# NG2094_Connector_A.net
KiCad netlist of a schematic drawn in Altium Designer
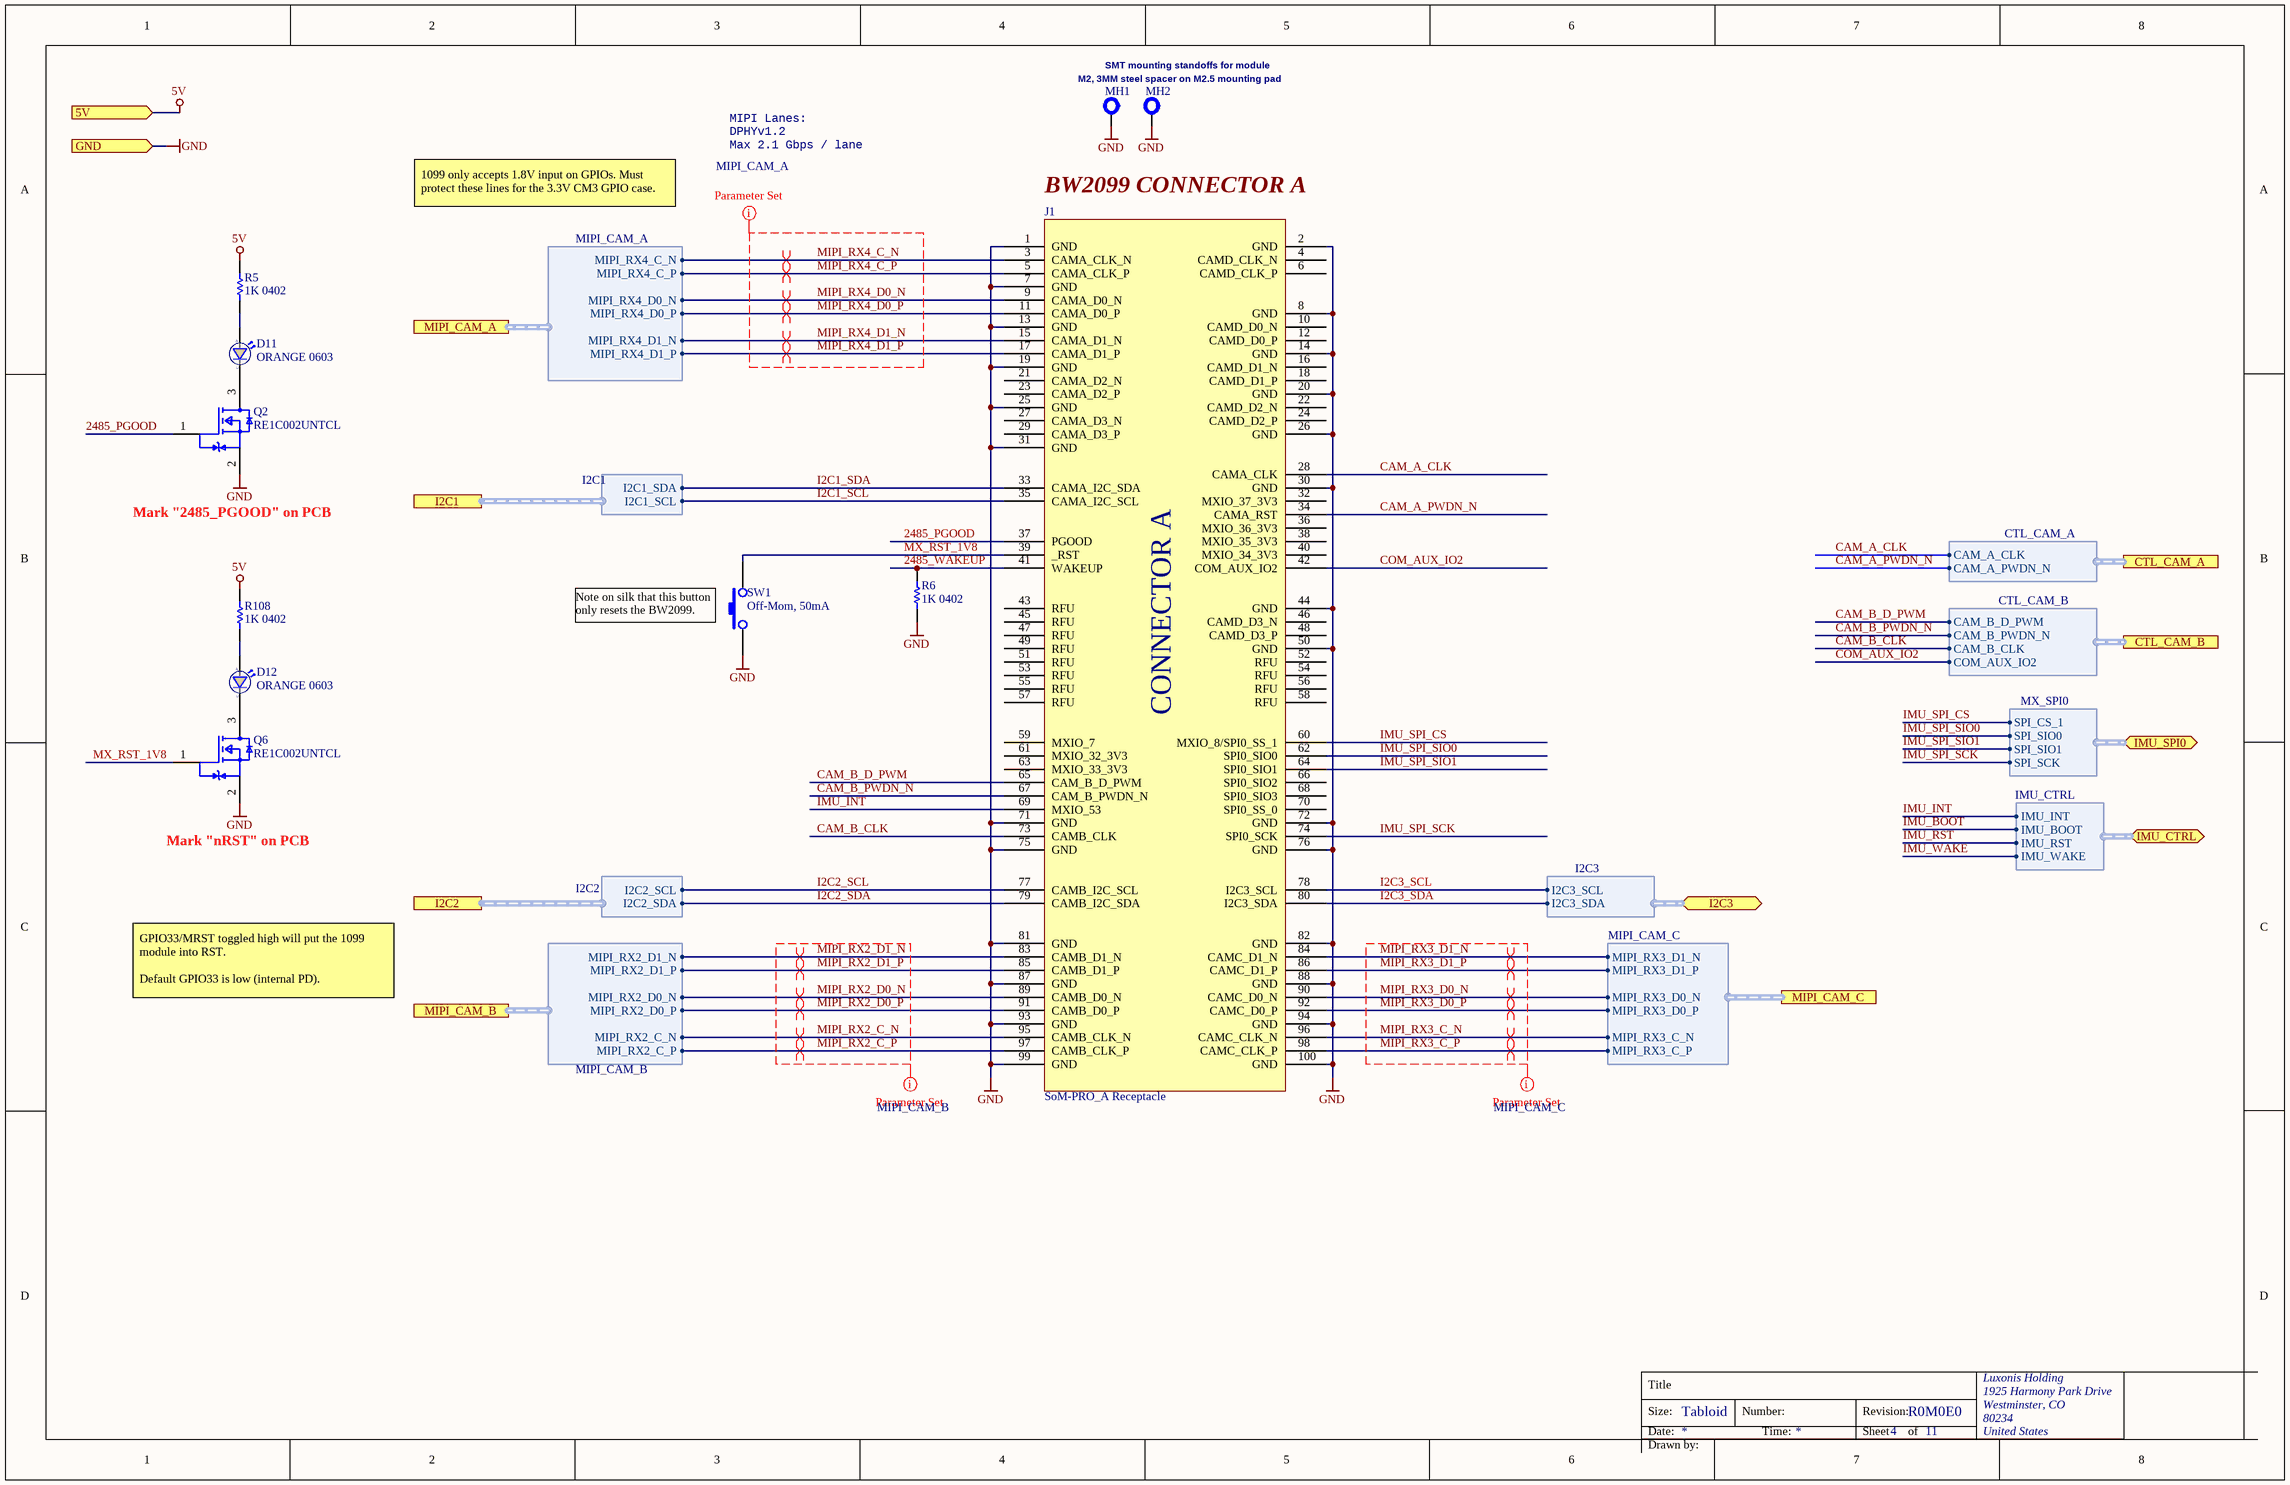
[diagram p0: NG2094_Connector_A.SchDoc]

(export (version "E")
  (design (tool "Eeschema 10.0.6"))
  (components
    (comp (ref "D11")
      (value "ORANGE 0603")
      (footprint "LuxonisMaster:SML_D1xx8W")
      (description "LED ORANGE DIFFUSED 0603 SMD Orange 605nm LED Indication - Discrete 2.2V 0603 (1608 Metric)")
      (libsource (lib "LuxonisMaster") (part "SML-D12D8WT86"))
    )
    (comp (ref "D12")
      (value "ORANGE 0603")
      (footprint "LuxonisMaster:SML_D1xx8W")
      (description "LED ORANGE DIFFUSED 0603 SMD Orange 605nm LED Indication - Discrete 2.2V 0603 (1608 Metric)")
      (libsource (lib "LuxonisMaster") (part "SML-D12D8WT86"))
    )
    (comp (ref "J1")
      (value "SoM-PRO_A Receptacle")
      (footprint "CON_A_BW2099_SoM_DF40HC-3.0-100DS-0.4V_minpad")
      (description "CONN RCPT 100POS 0.4MM SMD GOLD")
      (libsource (lib "BW2099_SoM") (part "DF40HC(3.0)-100DS-0.4V_SoM-PRO_A"))
    )
    (comp (ref "MH1")
      (value "M2, 3MM steel spacer on M2.5 mounting pad")
      (footprint "LuxonisMaster:9774030243R")
      (description "MP ROUND STANDOFF M2X0.4 STEEL 3MM")
      (libsource (lib "LuxonisMaster") (part "9774030243R"))
    )
    (comp (ref "MH2")
      (value "M2, 3MM steel spacer on M2.5 mounting pad")
      (footprint "LuxonisMaster:9774030243R")
      (description "MP ROUND STANDOFF M2X0.4 STEEL 3MM")
      (libsource (lib "LuxonisMaster") (part "9774030243R"))
    )
    (comp (ref "Q2")
      (value "RE1C002UNTCL")
      (footprint "LuxonisMaster:RE1C002UNTCL")
      (description "VISHAY - SI1062X-T1-GE3 - MOSFET Transistor, N Channel, 530 mA, 20 V, 0.35 ohm, 4.5 V, 1 V")
      (libsource (lib "LuxonisMaster") (part "RE1C002UNTCL"))
    )
    (comp (ref "Q6")
      (value "RE1C002UNTCL")
      (footprint "LuxonisMaster:RE1C002UNTCL")
      (description "VISHAY - SI1062X-T1-GE3 - MOSFET Transistor, N Channel, 530 mA, 20 V, 0.35 ohm, 4.5 V, 1 V")
      (libsource (lib "LuxonisMaster") (part "RE1C002UNTCL"))
    )
    (comp (ref "R5")
      (value "1K 0402")
      (footprint "RES_Altium_Vault_Generic:RESC0402(1005)_L")
      (fields (field (name "TOLERANCE") "1%"))
      (libsource (lib "LuxonisMaster") (part "RC0402FR-071KL"))
    )
    (comp (ref "R6")
      (value "1K 0402")
      (footprint "RES_Altium_Vault_Generic:RESC0402(1005)_L")
      (description "RES SMD 1K OHM 1% 1/16W 0402")
      (fields (field (name "TOLERANCE") "1%"))
      (libsource (lib "LuxonisMaster") (part "RC0402FR-071KL"))
    )
    (comp (ref "R108")
      (value "1K 0402")
      (footprint "RES_Altium_Vault_Generic:RESC0402(1005)_L")
      (fields (field (name "TOLERANCE") "1%"))
      (libsource (lib "LuxonisMaster") (part "RC0402FR-071KL"))
    )
    (comp (ref "SW1")
      (value "Off-Mom, 50mA")
      (footprint "LuxonisMaster:DTSM-32N-V")
      (description "SWITCH TACTILE SMT 3.5mm * 6mm , brown 160gf")
      (libsource (lib "LuxonisMaster") (part "DTSM-32N-V"))
    )
  )
  (nets
    (net (code "11") (name "/2485_PGOOD") (class "Default")
      (node (ref "J1") (pin "37") (pinfunction "PGOOD_37") (pintype "passive"))
      (node (ref "Q2") (pin "1") (pinfunction "Gate_1") (pintype "passive"))
    )
    (net (code "12") (name "/2485_WAKEUP") (class "Default")
      (node (ref "J1") (pin "41") (pinfunction "WAKEUP_41") (pintype "passive"))
      (node (ref "R6") (pin "2") (pinfunction "2_2") (pintype "passive"))
    )
    (net (code "13") (name "/CAM_A_CLK") (class "Default")
      (node (ref "J1") (pin "28") (pinfunction "CAMA_CLK_28") (pintype "passive"))
    )
    (net (code "14") (name "/CAM_A_PWDN_N") (class "Default")
      (node (ref "J1") (pin "34") (pinfunction "CAMA_RST_34") (pintype "passive"))
    )
    (net (code "15") (name "/CAM_B_CLK") (class "Default")
      (node (ref "J1") (pin "73") (pinfunction "CAMB_CLK_73") (pintype "passive"))
    )
    (net (code "16") (name "/CAM_B_D_PWM") (class "Default")
      (node (ref "J1") (pin "65") (pinfunction "CAM_B_D_PWM_65") (pintype "passive"))
    )
    (net (code "17") (name "/CAM_B_PWDN_N") (class "Default")
      (node (ref "J1") (pin "67") (pinfunction "CAM_B_PWDN_N_67") (pintype "passive"))
    )
    (net (code "18") (name "/COM_AUX_IO2") (class "Default")
      (node (ref "J1") (pin "42") (pinfunction "COM_AUX_IO2_42") (pintype "passive"))
    )
    (net (code "19") (name "/I2C1_SCL") (class "Default")
      (node (ref "J1") (pin "35") (pinfunction "CAMA_I2C_SCL_35") (pintype "passive"))
    )
    (net (code "20") (name "/I2C1_SDA") (class "Default")
      (node (ref "J1") (pin "33") (pinfunction "CAMA_I2C_SDA_33") (pintype "passive"))
    )
    (net (code "21") (name "/I2C2_SCL") (class "Default")
      (node (ref "J1") (pin "77") (pinfunction "CAMB_I2C_SCL_77") (pintype "passive"))
    )
    (net (code "22") (name "/I2C2_SDA") (class "Default")
      (node (ref "J1") (pin "79") (pinfunction "CAMB_I2C_SDA_79") (pintype "passive"))
    )
    (net (code "23") (name "/I2C3_SCL") (class "Default")
      (node (ref "J1") (pin "78") (pinfunction "I2C3_SCL_78") (pintype "passive"))
    )
    (net (code "24") (name "/I2C3_SDA") (class "Default")
      (node (ref "J1") (pin "80") (pinfunction "I2C3_SDA_80") (pintype "passive"))
    )
    (net (code "26") (name "/IMU_INT") (class "Default")
      (node (ref "J1") (pin "69") (pinfunction "MXIO_53_69") (pintype "passive"))
    )
    (net (code "28") (name "/IMU_SPI_CS") (class "Default")
      (node (ref "J1") (pin "60") (pinfunction "MXIO_8/SPI0_SS_1_60") (pintype "passive"))
    )
    (net (code "29") (name "/IMU_SPI_SCK") (class "Default")
      (node (ref "J1") (pin "74") (pinfunction "SPI0_SCK_74") (pintype "passive"))
    )
    (net (code "30") (name "/IMU_SPI_SIO0") (class "Default")
      (node (ref "J1") (pin "62") (pinfunction "SPI0_SIO0_62") (pintype "passive"))
    )
    (net (code "31") (name "/IMU_SPI_SIO1") (class "Default")
      (node (ref "J1") (pin "64") (pinfunction "SPI0_SIO1_64") (pintype "passive"))
    )
    (net (code "33") (name "/MIPI_RX2_C_N") (class "Default")
      (node (ref "J1") (pin "95") (pinfunction "CAMB_CLK_N_95") (pintype "passive"))
    )
    (net (code "34") (name "/MIPI_RX2_C_P") (class "Default")
      (node (ref "J1") (pin "97") (pinfunction "CAMB_CLK_P_97") (pintype "passive"))
    )
    (net (code "35") (name "/MIPI_RX2_D0_N") (class "Default")
      (node (ref "J1") (pin "89") (pinfunction "CAMB_D0_N_89") (pintype "passive"))
    )
    (net (code "36") (name "/MIPI_RX2_D0_P") (class "Default")
      (node (ref "J1") (pin "91") (pinfunction "CAMB_D0_P_91") (pintype "passive"))
    )
    (net (code "37") (name "/MIPI_RX2_D1_N") (class "Default")
      (node (ref "J1") (pin "83") (pinfunction "CAMB_D1_N_83") (pintype "passive"))
    )
    (net (code "38") (name "/MIPI_RX2_D1_P") (class "Default")
      (node (ref "J1") (pin "85") (pinfunction "CAMB_D1_P_85") (pintype "passive"))
    )
    (net (code "39") (name "/MIPI_RX3_C_N") (class "Default")
      (node (ref "J1") (pin "96") (pinfunction "CAMC_CLK_N_96") (pintype "passive"))
    )
    (net (code "40") (name "/MIPI_RX3_C_P") (class "Default")
      (node (ref "J1") (pin "98") (pinfunction "CAMC_CLK_P_98") (pintype "passive"))
    )
    (net (code "41") (name "/MIPI_RX3_D0_N") (class "Default")
      (node (ref "J1") (pin "90") (pinfunction "CAMC_D0_N_90") (pintype "passive"))
    )
    (net (code "42") (name "/MIPI_RX3_D0_P") (class "Default")
      (node (ref "J1") (pin "92") (pinfunction "CAMC_D0_P_92") (pintype "passive"))
    )
    (net (code "43") (name "/MIPI_RX3_D1_N") (class "Default")
      (node (ref "J1") (pin "84") (pinfunction "CAMC_D1_N_84") (pintype "passive"))
    )
    (net (code "44") (name "/MIPI_RX3_D1_P") (class "Default")
      (node (ref "J1") (pin "86") (pinfunction "CAMC_D1_P_86") (pintype "passive"))
    )
    (net (code "45") (name "/MIPI_RX4_C_N") (class "Default")
      (node (ref "J1") (pin "3") (pinfunction "CAMA_CLK_N_3") (pintype "passive"))
    )
    (net (code "46") (name "/MIPI_RX4_C_P") (class "Default")
      (node (ref "J1") (pin "5") (pinfunction "CAMA_CLK_P_5") (pintype "passive"))
    )
    (net (code "47") (name "/MIPI_RX4_D0_N") (class "Default")
      (node (ref "J1") (pin "9") (pinfunction "CAMA_D0_N_9") (pintype "passive"))
    )
    (net (code "48") (name "/MIPI_RX4_D0_P") (class "Default")
      (node (ref "J1") (pin "11") (pinfunction "CAMA_D0_P_11") (pintype "passive"))
    )
    (net (code "49") (name "/MIPI_RX4_D1_N") (class "Default")
      (node (ref "J1") (pin "15") (pinfunction "CAMA_D1_N_15") (pintype "passive"))
    )
    (net (code "50") (name "/MIPI_RX4_D1_P") (class "Default")
      (node (ref "J1") (pin "17") (pinfunction "CAMA_D1_P_17") (pintype "passive"))
    )
    (net (code "51") (name "/MX_RST_1V8") (class "Default")
      (node (ref "J1") (pin "39") (pinfunction "_RST_39") (pintype "passive"))
      (node (ref "Q6") (pin "1") (pinfunction "Gate_1") (pintype "passive"))
      (node (ref "SW1") (pin "2") (pinfunction "2_2") (pintype "passive"))
    )
    (net (code "62") (name "5V") (class "Default")
      (node (ref "R108") (pin "2") (pinfunction "2_2") (pintype "passive"))
      (node (ref "R5") (pin "2") (pinfunction "2_2") (pintype "passive"))
    )
    (net (code "63") (name "GND") (class "Default")
      (node (ref "J1") (pin "1") (pinfunction "GND_1") (pintype "passive"))
      (node (ref "J1") (pin "100") (pinfunction "GND_100") (pintype "passive"))
      (node (ref "J1") (pin "13") (pinfunction "GND_13") (pintype "passive"))
      (node (ref "J1") (pin "14") (pinfunction "GND_14") (pintype "passive"))
      (node (ref "J1") (pin "19") (pinfunction "GND_19") (pintype "passive"))
      (node (ref "J1") (pin "2") (pinfunction "GND_2") (pintype "passive"))
      (node (ref "J1") (pin "20") (pinfunction "GND_20") (pintype "passive"))
      (node (ref "J1") (pin "25") (pinfunction "GND_25") (pintype "passive"))
      (node (ref "J1") (pin "26") (pinfunction "GND_26") (pintype "passive"))
      (node (ref "J1") (pin "30") (pinfunction "GND_30") (pintype "passive"))
      (node (ref "J1") (pin "31") (pinfunction "GND_31") (pintype "passive"))
      (node (ref "J1") (pin "44") (pinfunction "GND_44") (pintype "passive"))
      (node (ref "J1") (pin "50") (pinfunction "GND_50") (pintype "passive"))
      (node (ref "J1") (pin "7") (pinfunction "GND_7") (pintype "passive"))
      (node (ref "J1") (pin "71") (pinfunction "GND_71") (pintype "passive"))
      (node (ref "J1") (pin "72") (pinfunction "GND_72") (pintype "passive"))
      (node (ref "J1") (pin "75") (pinfunction "GND_75") (pintype "passive"))
      (node (ref "J1") (pin "76") (pinfunction "GND_76") (pintype "passive"))
      (node (ref "J1") (pin "8") (pinfunction "GND_8") (pintype "passive"))
      (node (ref "J1") (pin "81") (pinfunction "GND_81") (pintype "passive"))
      (node (ref "J1") (pin "82") (pinfunction "GND_82") (pintype "passive"))
      (node (ref "J1") (pin "87") (pinfunction "GND_87") (pintype "passive"))
      (node (ref "J1") (pin "88") (pinfunction "GND_88") (pintype "passive"))
      (node (ref "J1") (pin "93") (pinfunction "GND_93") (pintype "passive"))
      (node (ref "J1") (pin "94") (pinfunction "GND_94") (pintype "passive"))
      (node (ref "J1") (pin "99") (pinfunction "GND_99") (pintype "passive"))
      (node (ref "MH1") (pin "1") (pintype "passive"))
      (node (ref "MH2") (pin "1") (pintype "passive"))
      (node (ref "Q2") (pin "2") (pinfunction "Source_2") (pintype "passive"))
      (node (ref "Q6") (pin "2") (pinfunction "Source_2") (pintype "passive"))
      (node (ref "R6") (pin "1") (pinfunction "1_1") (pintype "passive"))
      (node (ref "SW1") (pin "1") (pinfunction "1_1") (pintype "passive"))
    )
    (net (code "64") (name "Net-(D11-A)") (class "Default")
      (node (ref "D11") (pin "2") (pinfunction "A_2") (pintype "passive"))
      (node (ref "R5") (pin "1") (pinfunction "1_1") (pintype "passive"))
    )
    (net (code "65") (name "Net-(D11-C)") (class "Default")
      (node (ref "D11") (pin "1") (pinfunction "C_1") (pintype "passive"))
      (node (ref "Q2") (pin "3") (pinfunction "Drain_3") (pintype "passive"))
    )
    (net (code "66") (name "Net-(D12-A)") (class "Default")
      (node (ref "D12") (pin "2") (pinfunction "A_2") (pintype "passive"))
      (node (ref "R108") (pin "1") (pinfunction "1_1") (pintype "passive"))
    )
    (net (code "67") (name "Net-(D12-C)") (class "Default")
      (node (ref "D12") (pin "1") (pinfunction "C_1") (pintype "passive"))
      (node (ref "Q6") (pin "3") (pinfunction "Drain_3") (pintype "passive"))
    )
    (net (code "68") (name "unconnected-(J1-CAMA_D2_N-Pad21)") (class "Default")
      (node (ref "J1") (pin "21") (pinfunction "CAMA_D2_N_21") (pintype "passive"))
    )
    (net (code "69") (name "unconnected-(J1-CAMA_D2_P-Pad23)") (class "Default")
      (node (ref "J1") (pin "23") (pinfunction "CAMA_D2_P_23") (pintype "passive"))
    )
    (net (code "70") (name "unconnected-(J1-CAMA_D3_N-Pad27)") (class "Default")
      (node (ref "J1") (pin "27") (pinfunction "CAMA_D3_N_27") (pintype "passive"))
    )
    (net (code "71") (name "unconnected-(J1-CAMA_D3_P-Pad29)") (class "Default")
      (node (ref "J1") (pin "29") (pinfunction "CAMA_D3_P_29") (pintype "passive"))
    )
    (net (code "72") (name "unconnected-(J1-CAMD_CLK_N-Pad4)") (class "Default")
      (node (ref "J1") (pin "4") (pinfunction "CAMD_CLK_N_4") (pintype "passive"))
    )
    (net (code "73") (name "unconnected-(J1-CAMD_CLK_P-Pad6)") (class "Default")
      (node (ref "J1") (pin "6") (pinfunction "CAMD_CLK_P_6") (pintype "passive"))
    )
    (net (code "74") (name "unconnected-(J1-CAMD_D0_N-Pad10)") (class "Default")
      (node (ref "J1") (pin "10") (pinfunction "CAMD_D0_N_10") (pintype "passive"))
    )
    (net (code "75") (name "unconnected-(J1-CAMD_D0_P-Pad12)") (class "Default")
      (node (ref "J1") (pin "12") (pinfunction "CAMD_D0_P_12") (pintype "passive"))
    )
    (net (code "76") (name "unconnected-(J1-CAMD_D1_N-Pad16)") (class "Default")
      (node (ref "J1") (pin "16") (pinfunction "CAMD_D1_N_16") (pintype "passive"))
    )
    (net (code "77") (name "unconnected-(J1-CAMD_D1_P-Pad18)") (class "Default")
      (node (ref "J1") (pin "18") (pinfunction "CAMD_D1_P_18") (pintype "passive"))
    )
    (net (code "78") (name "unconnected-(J1-CAMD_D2_N-Pad22)") (class "Default")
      (node (ref "J1") (pin "22") (pinfunction "CAMD_D2_N_22") (pintype "passive"))
    )
    (net (code "79") (name "unconnected-(J1-CAMD_D2_P-Pad24)") (class "Default")
      (node (ref "J1") (pin "24") (pinfunction "CAMD_D2_P_24") (pintype "passive"))
    )
    (net (code "80") (name "unconnected-(J1-CAMD_D3_N-Pad46)") (class "Default")
      (node (ref "J1") (pin "46") (pinfunction "CAMD_D3_N_46") (pintype "passive"))
    )
    (net (code "81") (name "unconnected-(J1-CAMD_D3_P-Pad48)") (class "Default")
      (node (ref "J1") (pin "48") (pinfunction "CAMD_D3_P_48") (pintype "passive"))
    )
    (net (code "82") (name "unconnected-(J1-MXIO_7-Pad59)") (class "Default")
      (node (ref "J1") (pin "59") (pinfunction "MXIO_7_59") (pintype "passive"))
    )
    (net (code "83") (name "unconnected-(J1-MXIO_32_3V3-Pad61)") (class "Default")
      (node (ref "J1") (pin "61") (pinfunction "MXIO_32_3V3_61") (pintype "passive"))
    )
    (net (code "84") (name "unconnected-(J1-MXIO_33_3V3-Pad63)") (class "Default")
      (node (ref "J1") (pin "63") (pinfunction "MXIO_33_3V3_63") (pintype "passive"))
    )
    (net (code "85") (name "unconnected-(J1-MXIO_34_3V3-Pad40)") (class "Default")
      (node (ref "J1") (pin "40") (pinfunction "MXIO_34_3V3_40") (pintype "passive"))
    )
    (net (code "86") (name "unconnected-(J1-MXIO_35_3V3-Pad38)") (class "Default")
      (node (ref "J1") (pin "38") (pinfunction "MXIO_35_3V3_38") (pintype "passive"))
    )
    (net (code "87") (name "unconnected-(J1-MXIO_36_3V3-Pad36)") (class "Default")
      (node (ref "J1") (pin "36") (pinfunction "MXIO_36_3V3_36") (pintype "passive"))
    )
    (net (code "88") (name "unconnected-(J1-MXIO_37_3V3-Pad32)") (class "Default")
      (node (ref "J1") (pin "32") (pinfunction "MXIO_37_3V3_32") (pintype "passive"))
    )
    (net (code "89") (name "unconnected-(J1-RFU-Pad43)") (class "Default")
      (node (ref "J1") (pin "43") (pinfunction "RFU_43") (pintype "passive"))
    )
    (net (code "90") (name "unconnected-(J1-RFU-Pad45)") (class "Default")
      (node (ref "J1") (pin "45") (pinfunction "RFU_45") (pintype "passive"))
    )
    (net (code "91") (name "unconnected-(J1-RFU-Pad47)") (class "Default")
      (node (ref "J1") (pin "47") (pinfunction "RFU_47") (pintype "passive"))
    )
    (net (code "92") (name "unconnected-(J1-RFU-Pad49)") (class "Default")
      (node (ref "J1") (pin "49") (pinfunction "RFU_49") (pintype "passive"))
    )
    (net (code "93") (name "unconnected-(J1-RFU-Pad51)") (class "Default")
      (node (ref "J1") (pin "51") (pinfunction "RFU_51") (pintype "passive"))
    )
    (net (code "94") (name "unconnected-(J1-RFU-Pad52)") (class "Default")
      (node (ref "J1") (pin "52") (pinfunction "RFU_52") (pintype "passive"))
    )
    (net (code "95") (name "unconnected-(J1-RFU-Pad53)") (class "Default")
      (node (ref "J1") (pin "53") (pinfunction "RFU_53") (pintype "passive"))
    )
    (net (code "96") (name "unconnected-(J1-RFU-Pad54)") (class "Default")
      (node (ref "J1") (pin "54") (pinfunction "RFU_54") (pintype "passive"))
    )
    (net (code "97") (name "unconnected-(J1-RFU-Pad55)") (class "Default")
      (node (ref "J1") (pin "55") (pinfunction "RFU_55") (pintype "passive"))
    )
    (net (code "98") (name "unconnected-(J1-RFU-Pad56)") (class "Default")
      (node (ref "J1") (pin "56") (pinfunction "RFU_56") (pintype "passive"))
    )
    (net (code "99") (name "unconnected-(J1-RFU-Pad57)") (class "Default")
      (node (ref "J1") (pin "57") (pinfunction "RFU_57") (pintype "passive"))
    )
    (net (code "100") (name "unconnected-(J1-RFU-Pad58)") (class "Default")
      (node (ref "J1") (pin "58") (pinfunction "RFU_58") (pintype "passive"))
    )
    (net (code "101") (name "unconnected-(J1-SPI0_SIO2-Pad66)") (class "Default")
      (node (ref "J1") (pin "66") (pinfunction "SPI0_SIO2_66") (pintype "passive"))
    )
    (net (code "102") (name "unconnected-(J1-SPI0_SIO3-Pad68)") (class "Default")
      (node (ref "J1") (pin "68") (pinfunction "SPI0_SIO3_68") (pintype "passive"))
    )
    (net (code "103") (name "unconnected-(J1-SPI0_SS_0-Pad70)") (class "Default")
      (node (ref "J1") (pin "70") (pinfunction "SPI0_SS_0_70") (pintype "passive"))
    )
  )
)
